# MiniRoverShield.net
KiCad netlist of a schematic drawn in Altium Designer
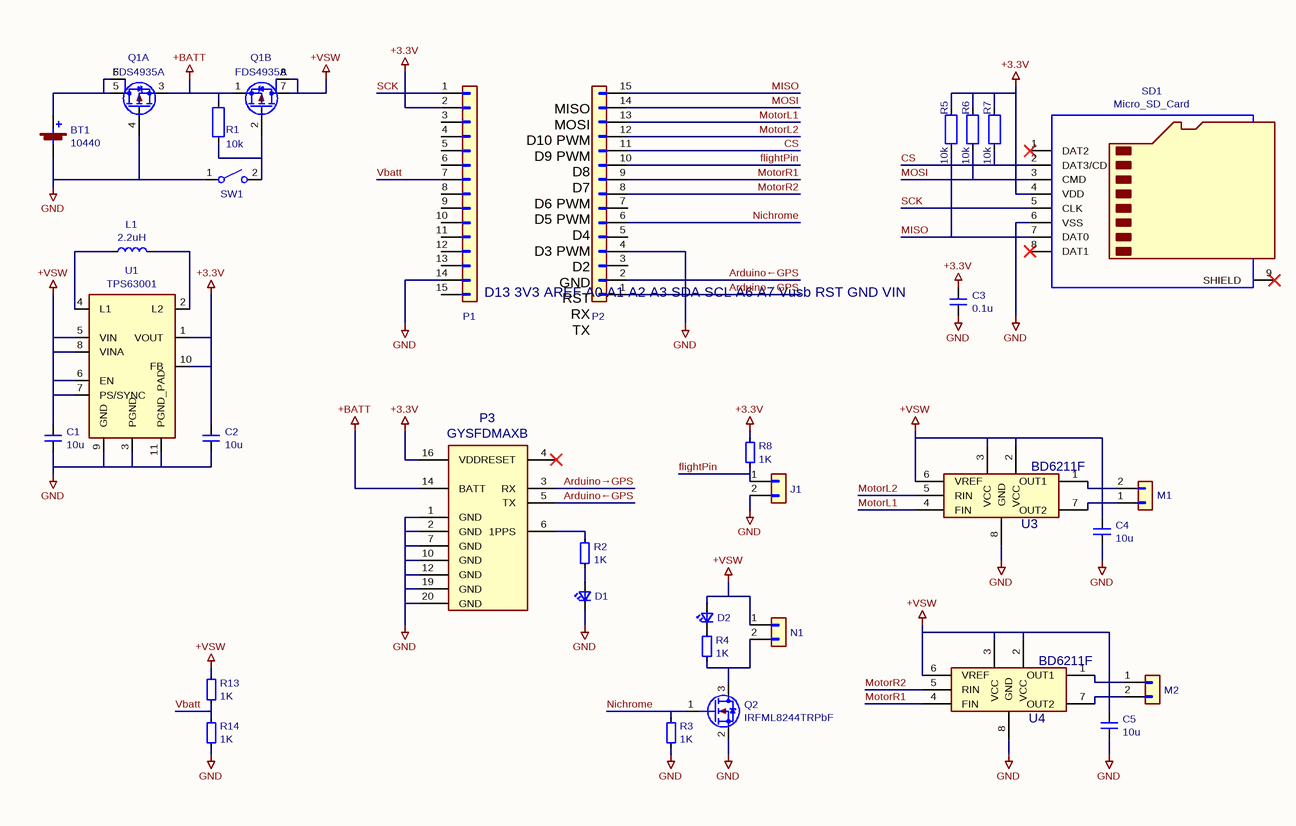
[diagram p0: MiniRoverShield.SchDoc]

(export (version "E")
  (design (tool "Eeschema 10.0.6"))
  (components
    (comp (ref "BT1") (value "10440") (libsource (lib "Device") (part "Battery_Cell")))
    (comp (ref "C1") (value "10u") (libsource (lib "Device") (part "C_Small")))
    (comp (ref "C2") (value "10u") (libsource (lib "Device") (part "C_Small")))
    (comp (ref "C3") (value "0.1u") (libsource (lib "Device") (part "C_Small")))
    (comp (ref "C4") (value "10u") (libsource (lib "Device") (part "C_Small")))
    (comp (ref "C5") (value "10u") (libsource (lib "Device") (part "C_Small")))
    (comp (ref "D1") (value "RED") (libsource (lib "Device") (part "LED_Small")))
    (comp (ref "D2") (value "RED") (libsource (lib "Device") (part "LED_Small")))
    (comp (ref "J1") (value "flightPin") (libsource (lib "Connector_Generic") (part "Conn_01x02")))
    (comp (ref "L1") (value "2.2uH") (libsource (lib "Device") (part "L")))
    (comp (ref "M1") (value "Motor") (libsource (lib "") (part "Conn_01x02_1")))
    (comp (ref "M2") (value "Motor") (libsource (lib "Connector_Generic") (part "Conn_01x02")))
    (comp (ref "N1") (value "Nichrome") (libsource (lib "Connector_Generic") (part "Conn_01x02")))
    (comp (ref "P1") (value "Arduino nano 33") (libsource (lib "") (part "Conn_01x15_1")))
    (comp (ref "P2") (value "Arduino nano 33") (libsource (lib "Connector_Generic") (part "Conn_01x15")))
    (comp (ref "P3")
      (value "GYSFDMAXB")
      (libsource (lib "MiniRoverShield-rescue") (part "GYSFDMAXB-user_library"))
    )
    (comp (ref "Q1")
      (value "FDS4935A")
      (libsource (lib "MiniRoverShield-rescue") (part "FDS4935A-user_library"))
    )
    (comp (ref "Q2") (value "IRFML8244TRPbF") (libsource (lib "Device") (part "Q_NMOS_GSD")))
    (comp (ref "R1") (value "10k") (libsource (lib "Device") (part "R")))
    (comp (ref "R2") (value "1K") (libsource (lib "Device") (part "R_Small")))
    (comp (ref "R3") (value "1K") (libsource (lib "Device") (part "R_Small")))
    (comp (ref "R4") (value "1K") (libsource (lib "Device") (part "R_Small")))
    (comp (ref "R5") (value "10k") (libsource (lib "Device") (part "R")))
    (comp (ref "R6") (value "10k") (libsource (lib "Device") (part "R")))
    (comp (ref "R7") (value "10k") (libsource (lib "Device") (part "R")))
    (comp (ref "R8") (value "1K") (libsource (lib "Device") (part "R_Small")))
    (comp (ref "R13") (value "1K") (libsource (lib "Device") (part "R_Small")))
    (comp (ref "R14") (value "1K") (libsource (lib "Device") (part "R_Small")))
    (comp (ref "SD1")
      (value "Micro_SD_Card")
      (libsource (lib "MiniRoverShield-rescue") (part "Micro_SD_Card-Connector"))
    )
    (comp (ref "SW1") (value "Power") (libsource (lib "Switch") (part "SW_SPST")))
    (comp (ref "U1")
      (value "TPS63001")
      (libsource (lib "MiniRoverShield-rescue") (part "TPS63000-user_library"))
    )
    (comp (ref "U3")
      (value "BD6211F")
      (libsource (lib "MiniRoverShield-rescue") (part "BD6231F_2-user_library"))
    )
    (comp (ref "U4")
      (value "BD6211F")
      (libsource (lib "MiniRoverShield-rescue") (part "BD6231F_2-user_library"))
    )
  )
  (nets
    (net (code "1") (name "+3.3V") (class "Default")
      (node (ref "C2") (pin "1") (pinfunction "1_1") (pintype "passive"))
      (node (ref "C3") (pin "1") (pinfunction "1_1") (pintype "passive"))
      (node (ref "P1") (pin "2") (pinfunction "Pin_2_2") (pintype "passive"))
      (node (ref "P3") (pin "16") (pinfunction "VDD_16") (pintype "passive"))
      (node (ref "R5") (pin "1") (pinfunction "1_1") (pintype "passive"))
      (node (ref "R6") (pin "1") (pinfunction "1_1") (pintype "passive"))
      (node (ref "R7") (pin "1") (pinfunction "1_1") (pintype "passive"))
      (node (ref "R8") (pin "1") (pinfunction "1_1") (pintype "passive"))
      (node (ref "SD1") (pin "4") (pinfunction "VDD_4") (pintype "passive"))
      (node (ref "U1") (pin "1") (pinfunction "VOUT_1") (pintype "passive"))
      (node (ref "U1") (pin "10") (pinfunction "FB_10") (pintype "passive"))
    )
    (net (code "2") (name "+BATT") (class "Default")
      (node (ref "P3") (pin "14") (pinfunction "BATT_14") (pintype "passive"))
      (node (ref "Q1") (pin "1") (pinfunction "S_1") (pintype "passive"))
      (node (ref "Q1") (pin "3") (pinfunction "S_3") (pintype "passive"))
      (node (ref "R1") (pin "1") (pinfunction "1_1") (pintype "passive"))
    )
    (net (code "3") (name "+VSW") (class "Default")
      (node (ref "C1") (pin "1") (pinfunction "1_1") (pintype "passive"))
      (node (ref "C4") (pin "1") (pinfunction "1_1") (pintype "passive"))
      (node (ref "C5") (pin "1") (pinfunction "1_1") (pintype "passive"))
      (node (ref "D2") (pin "2") (pinfunction "A_2") (pintype "passive"))
      (node (ref "N1") (pin "1") (pinfunction "Pin_1_1") (pintype "passive"))
      (node (ref "Q1") (pin "7") (pinfunction "D_7") (pintype "passive"))
      (node (ref "Q1") (pin "8") (pinfunction "D_8") (pintype "passive"))
      (node (ref "R13") (pin "1") (pinfunction "1_1") (pintype "passive"))
      (node (ref "U1") (pin "5") (pinfunction "VIN_5") (pintype "passive"))
      (node (ref "U1") (pin "6") (pinfunction "EN_6") (pintype "passive"))
      (node (ref "U1") (pin "7") (pinfunction "PS/SYNC_7") (pintype "passive"))
      (node (ref "U1") (pin "8") (pinfunction "VINA_8") (pintype "passive"))
      (node (ref "U3") (pin "2") (pinfunction "VCC_2") (pintype "passive"))
      (node (ref "U3") (pin "3") (pinfunction "VCC_3") (pintype "passive"))
      (node (ref "U3") (pin "6") (pinfunction "VREF_6") (pintype "passive"))
      (node (ref "U4") (pin "2") (pinfunction "VCC_2") (pintype "passive"))
      (node (ref "U4") (pin "3") (pinfunction "VCC_3") (pintype "passive"))
      (node (ref "U4") (pin "6") (pinfunction "VREF_6") (pintype "passive"))
    )
    (net (code "4") (name "/Arduino←GPS") (class "Default")
      (node (ref "P2") (pin "2") (pinfunction "Pin_2_2") (pintype "passive"))
      (node (ref "P3") (pin "5") (pinfunction "TX_5") (pintype "passive"))
    )
    (net (code "5") (name "/Arduino→GPS") (class "Default")
      (node (ref "P2") (pin "1") (pinfunction "Pin_1_1") (pintype "passive"))
      (node (ref "P3") (pin "3") (pinfunction "RX_3") (pintype "passive"))
    )
    (net (code "6") (name "/CS") (class "Default")
      (node (ref "P2") (pin "11") (pinfunction "Pin_11_11") (pintype "passive"))
      (node (ref "R7") (pin "2") (pinfunction "2_2") (pintype "passive"))
      (node (ref "SD1") (pin "2") (pinfunction "DAT3/CD_2") (pintype "passive"))
    )
    (net (code "7") (name "/MISO") (class "Default")
      (node (ref "P2") (pin "15") (pinfunction "Pin_15_15") (pintype "passive"))
      (node (ref "R5") (pin "2") (pinfunction "2_2") (pintype "passive"))
      (node (ref "SD1") (pin "7") (pinfunction "DAT0_7") (pintype "passive"))
    )
    (net (code "8") (name "/MOSI") (class "Default")
      (node (ref "P2") (pin "14") (pinfunction "Pin_14_14") (pintype "passive"))
      (node (ref "R6") (pin "2") (pinfunction "2_2") (pintype "passive"))
      (node (ref "SD1") (pin "3") (pinfunction "CMD_3") (pintype "passive"))
    )
    (net (code "9") (name "/MotorL1") (class "Default")
      (node (ref "P2") (pin "13") (pinfunction "Pin_13_13") (pintype "passive"))
      (node (ref "U3") (pin "4") (pinfunction "FIN_4") (pintype "passive"))
    )
    (net (code "10") (name "/MotorL2") (class "Default")
      (node (ref "P2") (pin "12") (pinfunction "Pin_12_12") (pintype "passive"))
      (node (ref "U3") (pin "5") (pinfunction "RIN_5") (pintype "passive"))
    )
    (net (code "11") (name "/MotorR1") (class "Default")
      (node (ref "P2") (pin "9") (pinfunction "Pin_9_9") (pintype "passive"))
      (node (ref "U4") (pin "4") (pinfunction "FIN_4") (pintype "passive"))
    )
    (net (code "12") (name "/MotorR2") (class "Default")
      (node (ref "P2") (pin "8") (pinfunction "Pin_8_8") (pintype "passive"))
      (node (ref "U4") (pin "5") (pinfunction "RIN_5") (pintype "passive"))
    )
    (net (code "13") (name "/Nichrome") (class "Default")
      (node (ref "P2") (pin "6") (pinfunction "Pin_6_6") (pintype "passive"))
      (node (ref "Q2") (pin "1") (pinfunction "G_1") (pintype "passive"))
      (node (ref "R3") (pin "1") (pinfunction "1_1") (pintype "passive"))
    )
    (net (code "14") (name "/SCK") (class "Default")
      (node (ref "P1") (pin "1") (pinfunction "Pin_1_1") (pintype "passive"))
      (node (ref "SD1") (pin "5") (pinfunction "CLK_5") (pintype "passive"))
    )
    (net (code "15") (name "/Vbatt") (class "Default")
      (node (ref "P1") (pin "7") (pinfunction "Pin_7_7") (pintype "passive"))
      (node (ref "R13") (pin "2") (pinfunction "2_2") (pintype "passive"))
      (node (ref "R14") (pin "1") (pinfunction "1_1") (pintype "passive"))
    )
    (net (code "16") (name "/flightPin") (class "Default")
      (node (ref "J1") (pin "1") (pinfunction "Pin_1_1") (pintype "passive"))
      (node (ref "P2") (pin "10") (pinfunction "Pin_10_10") (pintype "passive"))
      (node (ref "R8") (pin "2") (pinfunction "2_2") (pintype "passive"))
    )
    (net (code "17") (name "GND") (class "Default")
      (node (ref "BT1") (pin "2") (pinfunction "-_2") (pintype "passive"))
      (node (ref "C1") (pin "2") (pinfunction "2_2") (pintype "passive"))
      (node (ref "C2") (pin "2") (pinfunction "2_2") (pintype "passive"))
      (node (ref "C3") (pin "2") (pinfunction "2_2") (pintype "passive"))
      (node (ref "C4") (pin "2") (pinfunction "2_2") (pintype "passive"))
      (node (ref "C5") (pin "2") (pinfunction "2_2") (pintype "passive"))
      (node (ref "D1") (pin "1") (pinfunction "K_1") (pintype "passive"))
      (node (ref "J1") (pin "2") (pinfunction "Pin_2_2") (pintype "passive"))
      (node (ref "P1") (pin "14") (pinfunction "Pin_14_14") (pintype "passive"))
      (node (ref "P2") (pin "4") (pinfunction "Pin_4_4") (pintype "passive"))
      (node (ref "P3") (pin "1") (pinfunction "GND_1") (pintype "passive"))
      (node (ref "P3") (pin "10") (pinfunction "GND_10") (pintype "passive"))
      (node (ref "P3") (pin "12") (pinfunction "GND_12") (pintype "passive"))
      (node (ref "P3") (pin "19") (pinfunction "GND_19") (pintype "passive"))
      (node (ref "P3") (pin "2") (pinfunction "GND_2") (pintype "passive"))
      (node (ref "P3") (pin "20") (pinfunction "GND_20") (pintype "passive"))
      (node (ref "P3") (pin "7") (pinfunction "GND_7") (pintype "passive"))
      (node (ref "Q1") (pin "4") (pinfunction "G_4") (pintype "passive"))
      (node (ref "Q2") (pin "2") (pinfunction "S_2") (pintype "passive"))
      (node (ref "R14") (pin "2") (pinfunction "2_2") (pintype "passive"))
      (node (ref "R3") (pin "2") (pinfunction "2_2") (pintype "passive"))
      (node (ref "SD1") (pin "6") (pinfunction "VSS_6") (pintype "passive"))
      (node (ref "SW1") (pin "1") (pinfunction "A_1") (pintype "passive"))
      (node (ref "U1") (pin "11") (pinfunction "PGND_PAD_11") (pintype "passive"))
      (node (ref "U1") (pin "3") (pinfunction "PGND_3") (pintype "passive"))
      (node (ref "U1") (pin "9") (pinfunction "GND_9") (pintype "passive"))
      (node (ref "U3") (pin "8") (pinfunction "GND_8") (pintype "passive"))
      (node (ref "U4") (pin "8") (pinfunction "GND_8") (pintype "passive"))
    )
    (net (code "18") (name "Net-(BT1-+)") (class "Default")
      (node (ref "BT1") (pin "1") (pinfunction "+_1") (pintype "passive"))
      (node (ref "Q1") (pin "5") (pinfunction "D_5") (pintype "passive"))
      (node (ref "Q1") (pin "6") (pinfunction "D_6") (pintype "passive"))
    )
    (net (code "19") (name "Net-(D1-A)") (class "Default")
      (node (ref "D1") (pin "2") (pinfunction "A_2") (pintype "passive"))
      (node (ref "R2") (pin "2") (pinfunction "2_2") (pintype "passive"))
    )
    (net (code "20") (name "Net-(D2-K)") (class "Default")
      (node (ref "D2") (pin "1") (pinfunction "K_1") (pintype "passive"))
      (node (ref "R4") (pin "1") (pinfunction "1_1") (pintype "passive"))
    )
    (net (code "21") (name "Net-(M1-Pin_1)") (class "Default")
      (node (ref "M1") (pin "1") (pinfunction "Pin_1_1") (pintype "passive"))
      (node (ref "U3") (pin "7") (pinfunction "OUT2_7") (pintype "passive"))
    )
    (net (code "22") (name "Net-(M1-Pin_2)") (class "Default")
      (node (ref "M1") (pin "2") (pinfunction "Pin_2_2") (pintype "passive"))
      (node (ref "U3") (pin "1") (pinfunction "OUT1_1") (pintype "passive"))
    )
    (net (code "23") (name "Net-(M2-Pin_1)") (class "Default")
      (node (ref "M2") (pin "1") (pinfunction "Pin_1_1") (pintype "passive"))
      (node (ref "U4") (pin "1") (pinfunction "OUT1_1") (pintype "passive"))
    )
    (net (code "24") (name "Net-(M2-Pin_2)") (class "Default")
      (node (ref "M2") (pin "2") (pinfunction "Pin_2_2") (pintype "passive"))
      (node (ref "U4") (pin "7") (pinfunction "OUT2_7") (pintype "passive"))
    )
    (net (code "25") (name "Net-(N1-Pin_2)") (class "Default")
      (node (ref "N1") (pin "2") (pinfunction "Pin_2_2") (pintype "passive"))
      (node (ref "Q2") (pin "3") (pinfunction "D_3") (pintype "passive"))
      (node (ref "R4") (pin "2") (pinfunction "2_2") (pintype "passive"))
    )
    (net (code "26") (name "Net-(P3-1PPS)") (class "Default")
      (node (ref "P3") (pin "6") (pinfunction "1PPS_6") (pintype "passive"))
      (node (ref "R2") (pin "1") (pinfunction "1_1") (pintype "passive"))
    )
    (net (code "27") (name "Net-(Q1B-4G)") (class "Default")
      (node (ref "Q1") (pin "2") (pinfunction "4G_2") (pintype "passive"))
      (node (ref "R1") (pin "2") (pinfunction "2_2") (pintype "passive"))
      (node (ref "SW1") (pin "2") (pinfunction "B_2") (pintype "passive"))
    )
    (net (code "28") (name "Net-(U1-L1)") (class "Default")
      (node (ref "L1") (pin "1") (pinfunction "1_1") (pintype "passive"))
      (node (ref "U1") (pin "4") (pinfunction "L1_4") (pintype "passive"))
    )
    (net (code "29") (name "Net-(U1-L2)") (class "Default")
      (node (ref "L1") (pin "2") (pinfunction "2_2") (pintype "passive"))
      (node (ref "U1") (pin "2") (pinfunction "L2_2") (pintype "passive"))
    )
    (net (code "30") (name "unconnected-(P1-Pin_3-Pad3)") (class "Default")
      (node (ref "P1") (pin "3") (pinfunction "Pin_3_3") (pintype "passive"))
    )
    (net (code "31") (name "unconnected-(P1-Pin_4-Pad4)") (class "Default")
      (node (ref "P1") (pin "4") (pinfunction "Pin_4_4") (pintype "passive"))
    )
    (net (code "32") (name "unconnected-(P1-Pin_5-Pad5)") (class "Default")
      (node (ref "P1") (pin "5") (pinfunction "Pin_5_5") (pintype "passive"))
    )
    (net (code "33") (name "unconnected-(P1-Pin_6-Pad6)") (class "Default")
      (node (ref "P1") (pin "6") (pinfunction "Pin_6_6") (pintype "passive"))
    )
    (net (code "34") (name "unconnected-(P1-Pin_8-Pad8)") (class "Default")
      (node (ref "P1") (pin "8") (pinfunction "Pin_8_8") (pintype "passive"))
    )
    (net (code "35") (name "unconnected-(P1-Pin_9-Pad9)") (class "Default")
      (node (ref "P1") (pin "9") (pinfunction "Pin_9_9") (pintype "passive"))
    )
    (net (code "36") (name "unconnected-(P1-Pin_10-Pad10)") (class "Default")
      (node (ref "P1") (pin "10") (pinfunction "Pin_10_10") (pintype "passive"))
    )
    (net (code "37") (name "unconnected-(P1-Pin_11-Pad11)") (class "Default")
      (node (ref "P1") (pin "11") (pinfunction "Pin_11_11") (pintype "passive"))
    )
    (net (code "38") (name "unconnected-(P1-Pin_12-Pad12)") (class "Default")
      (node (ref "P1") (pin "12") (pinfunction "Pin_12_12") (pintype "passive"))
    )
    (net (code "39") (name "unconnected-(P1-Pin_13-Pad13)") (class "Default")
      (node (ref "P1") (pin "13") (pinfunction "Pin_13_13") (pintype "passive"))
    )
    (net (code "40") (name "unconnected-(P1-Pin_15-Pad15)") (class "Default")
      (node (ref "P1") (pin "15") (pinfunction "Pin_15_15") (pintype "passive"))
    )
    (net (code "41") (name "unconnected-(P2-Pin_3-Pad3)") (class "Default")
      (node (ref "P2") (pin "3") (pinfunction "Pin_3_3") (pintype "passive"))
    )
    (net (code "42") (name "unconnected-(P2-Pin_5-Pad5)") (class "Default")
      (node (ref "P2") (pin "5") (pinfunction "Pin_5_5") (pintype "passive"))
    )
    (net (code "43") (name "unconnected-(P2-Pin_7-Pad7)") (class "Default")
      (node (ref "P2") (pin "7") (pinfunction "Pin_7_7") (pintype "passive"))
    )
    (net (code "44") (name "unconnected-(P3-RESET-Pad4)") (class "Default")
      (node (ref "P3") (pin "4") (pinfunction "RESET_4") (pintype "passive+no_connect"))
    )
    (net (code "45") (name "unconnected-(SD1-DAT1-Pad8)") (class "Default")
      (node (ref "SD1") (pin "8") (pinfunction "DAT1_8") (pintype "passive+no_connect"))
    )
    (net (code "46") (name "unconnected-(SD1-DAT2-Pad1)") (class "Default")
      (node (ref "SD1") (pin "1") (pinfunction "DAT2_1") (pintype "passive+no_connect"))
    )
    (net (code "47") (name "unconnected-(SD1-SHIELD-Pad9)") (class "Default")
      (node (ref "SD1") (pin "9") (pinfunction "SHIELD_9") (pintype "passive+no_connect"))
    )
  )
)
